# Hub_03.net
KiCad netlist of a schematic drawn in EAGLE
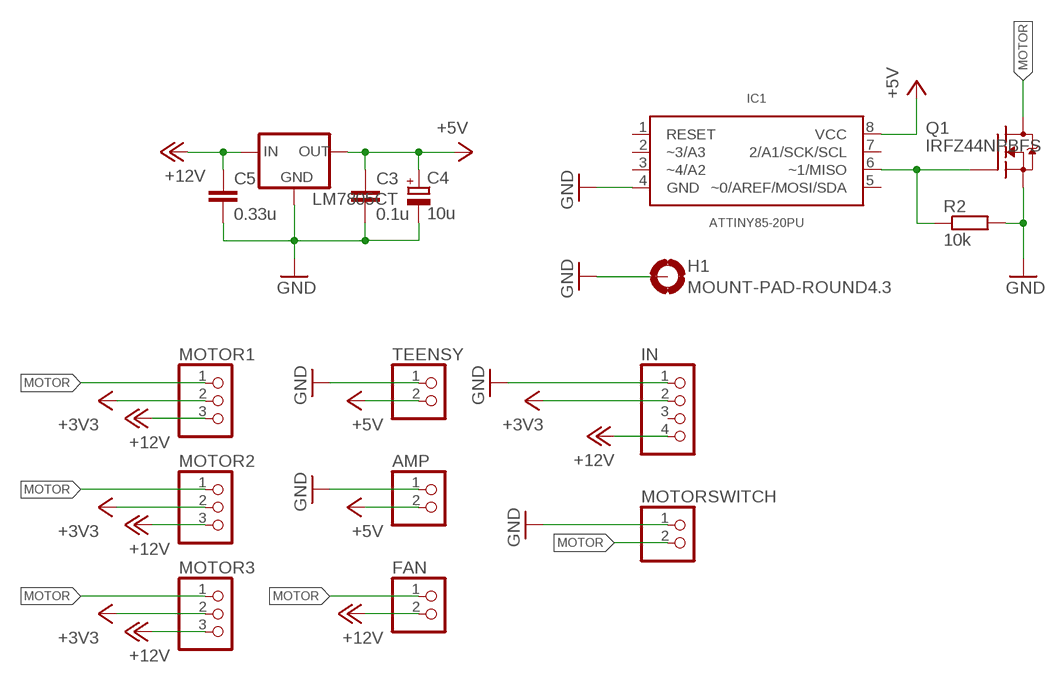
[diagram p0: schematic, sheet 1]

(export (version "E")
  (design (tool "Eeschema 10.0.6"))
  (components
    (comp (ref "AMP")
      (value "PINHD-1X2")
      (footprint "eagle-import:1X02")
      (libsource (lib "eagle-import") (part "PINHD-1X2"))
    )
    (comp (ref "C3")
      (value "0.1u")
      (footprint "eagle-import:C025-024X044")
      (libsource (lib "eagle-import") (part "C-EU025-024X044"))
    )
    (comp (ref "C4")
      (value "10u")
      (footprint "eagle-import:E2,5-6E")
      (libsource (lib "eagle-import") (part "CPOL-EUE2,5-6E"))
    )
    (comp (ref "C5")
      (value "0.33u")
      (footprint "eagle-import:C025-024X044")
      (libsource (lib "eagle-import") (part "C-EU025-024X044"))
    )
    (comp (ref "FAN")
      (value "PINHD-1X2")
      (footprint "eagle-import:1X02")
      (libsource (lib "eagle-import") (part "PINHD-1X2"))
    )
    (comp (ref "H1")
      (value "MOUNT-PAD-ROUND4.3")
      (footprint "eagle-import:4,3-PAD")
      (libsource (lib "eagle-import") (part "MOUNT-PAD-ROUND4.3"))
    )
    (comp (ref "IC1")
      (value "ATTINY85-20PU")
      (footprint "eagle-import:DIP08")
      (libsource (lib "eagle-import") (part "ATTINY85-20PU"))
    )
    (comp (ref "IN")
      (value "PINHD-1X4")
      (footprint "eagle-import:1X04")
      (libsource (lib "eagle-import") (part "PINHD-1X4"))
    )
    (comp (ref "LM7805CT")
      (value "78XXS")
      (footprint "eagle-import:78XXS")
      (libsource (lib "eagle-import") (part "78XXS"))
    )
    (comp (ref "MOTOR1")
      (value "PINHD-1X3")
      (footprint "eagle-import:1X03")
      (libsource (lib "eagle-import") (part "PINHD-1X3"))
    )
    (comp (ref "MOTOR2")
      (value "PINHD-1X3")
      (footprint "eagle-import:1X03")
      (libsource (lib "eagle-import") (part "PINHD-1X3"))
    )
    (comp (ref "MOTOR3")
      (value "PINHD-1X3")
      (footprint "eagle-import:1X03")
      (libsource (lib "eagle-import") (part "PINHD-1X3"))
    )
    (comp (ref "MOTORSWITCH")
      (value "PINHD-1X2")
      (footprint "eagle-import:1X02")
      (libsource (lib "eagle-import") (part "PINHD-1X2"))
    )
    (comp (ref "Q1")
      (value "IRFZ44NPBFS")
      (footprint "eagle-import:TO220-3S")
      (libsource (lib "eagle-import") (part "IRFZ44NPBFS"))
    )
    (comp (ref "R2")
      (value "10k")
      (footprint "eagle-import:0204_7")
      (libsource (lib "eagle-import") (part "R-EU_0204/7"))
    )
    (comp (ref "TEENSY")
      (value "PINHD-1X2")
      (footprint "eagle-import:1X02")
      (libsource (lib "eagle-import") (part "PINHD-1X2"))
    )
  )
  (nets
    (net (code "1") (name "+3V3") (class "Default")
      (node (ref "IN") (pin "2") (pinfunction "2_2") (pintype "passive"))
      (node (ref "MOTOR1") (pin "2") (pinfunction "2_2") (pintype "passive"))
      (node (ref "MOTOR2") (pin "2") (pinfunction "2_2") (pintype "passive"))
      (node (ref "MOTOR3") (pin "2") (pinfunction "2_2") (pintype "passive"))
    )
    (net (code "2") (name "+5V") (class "Default")
      (node (ref "AMP") (pin "2") (pinfunction "2_2") (pintype "passive"))
      (node (ref "C3") (pin "1") (pinfunction "1_1") (pintype "passive"))
      (node (ref "C4") (pin "+") (pinfunction "+_+") (pintype "passive"))
      (node (ref "IC1") (pin "8") (pinfunction "VCC_8") (pintype "bidirectional"))
      (node (ref "LM7805CT") (pin "OUT") (pinfunction "OUT_OUT") (pintype "passive"))
      (node (ref "TEENSY") (pin "2") (pinfunction "2_2") (pintype "passive"))
    )
    (net (code "3") (name "+12V") (class "Default")
      (node (ref "C5") (pin "1") (pinfunction "1_1") (pintype "passive"))
      (node (ref "FAN") (pin "2") (pinfunction "2_2") (pintype "passive"))
      (node (ref "IN") (pin "4") (pinfunction "4_4") (pintype "passive"))
      (node (ref "LM7805CT") (pin "IN") (pinfunction "IN_IN") (pintype "input"))
      (node (ref "MOTOR1") (pin "3") (pinfunction "3_3") (pintype "passive"))
      (node (ref "MOTOR2") (pin "3") (pinfunction "3_3") (pintype "passive"))
      (node (ref "MOTOR3") (pin "3") (pinfunction "3_3") (pintype "passive"))
    )
    (net (code "4") (name "GND") (class "Default")
      (node (ref "AMP") (pin "1") (pinfunction "1_1") (pintype "passive"))
      (node (ref "C3") (pin "2") (pinfunction "2_2") (pintype "passive"))
      (node (ref "C4") (pin "-") (pinfunction "-_-") (pintype "passive"))
      (node (ref "C5") (pin "2") (pinfunction "2_2") (pintype "passive"))
      (node (ref "H1") (pin "B4,3") (pinfunction "MOUNT_B4,3") (pintype "passive"))
      (node (ref "IC1") (pin "4") (pinfunction "GND_4") (pintype "bidirectional"))
      (node (ref "IN") (pin "1") (pinfunction "1_1") (pintype "passive"))
      (node (ref "LM7805CT") (pin "GND") (pinfunction "GND_GND") (pintype "input"))
      (node (ref "MOTORSWITCH") (pin "1") (pinfunction "1_1") (pintype "passive"))
      (node (ref "Q1") (pin "S") (pinfunction "S_S") (pintype "passive"))
      (node (ref "R2") (pin "2") (pinfunction "2_2") (pintype "passive"))
      (node (ref "TEENSY") (pin "1") (pinfunction "1_1") (pintype "passive"))
    )
    (net (code "5") (name "MOTOR") (class "Default")
      (node (ref "FAN") (pin "1") (pinfunction "1_1") (pintype "passive"))
      (node (ref "MOTOR1") (pin "1") (pinfunction "1_1") (pintype "passive"))
      (node (ref "MOTOR2") (pin "1") (pinfunction "1_1") (pintype "passive"))
      (node (ref "MOTOR3") (pin "1") (pinfunction "1_1") (pintype "passive"))
      (node (ref "MOTORSWITCH") (pin "2") (pinfunction "2_2") (pintype "passive"))
      (node (ref "Q1") (pin "D") (pinfunction "D_D") (pintype "passive"))
    )
    (net (code "6") (name "Net-(IC1-~{1{slash}MISO})") (class "Default")
      (node (ref "IC1") (pin "6") (pinfunction "~{1/MISO}_6") (pintype "bidirectional"))
      (node (ref "Q1") (pin "G") (pinfunction "G_G") (pintype "passive"))
      (node (ref "R2") (pin "1") (pinfunction "1_1") (pintype "passive"))
    )
    (net (code "7") (name "unconnected-(IC1-2{slash}A1{slash}SCK{slash}SCL-Pad7)") (class "Default")
      (node (ref "IC1") (pin "7") (pinfunction "2/A1/SCK/SCL_7") (pintype "bidirectional"))
    )
    (net (code "8") (name "unconnected-(IC1-RESET-Pad1)") (class "Default")
      (node (ref "IC1") (pin "1") (pinfunction "RESET_1") (pintype "bidirectional"))
    )
    (net (code "9") (name "unconnected-(IC1-~{0{slash}AREF{slash}MOSI{slash}SDA}-Pad5)") (class "Default")
      (node (ref "IC1") (pin "5") (pinfunction "~{0/AREF/MOSI/SDA}_5") (pintype "bidirectional"))
    )
    (net (code "10") (name "unconnected-(IC1-~{3{slash}A3}-Pad2)") (class "Default")
      (node (ref "IC1") (pin "2") (pinfunction "~{3/A3}_2") (pintype "bidirectional"))
    )
    (net (code "11") (name "unconnected-(IC1-~{4{slash}A2}-Pad3)") (class "Default")
      (node (ref "IC1") (pin "3") (pinfunction "~{4/A2}_3") (pintype "bidirectional"))
    )
    (net (code "12") (name "unconnected-(IN-Pad3)") (class "Default")
      (node (ref "IN") (pin "3") (pinfunction "3_3") (pintype "passive"))
    )
  )
)
